# Ethernet1.net
KiCad netlist of a schematic drawn in Altium Designer
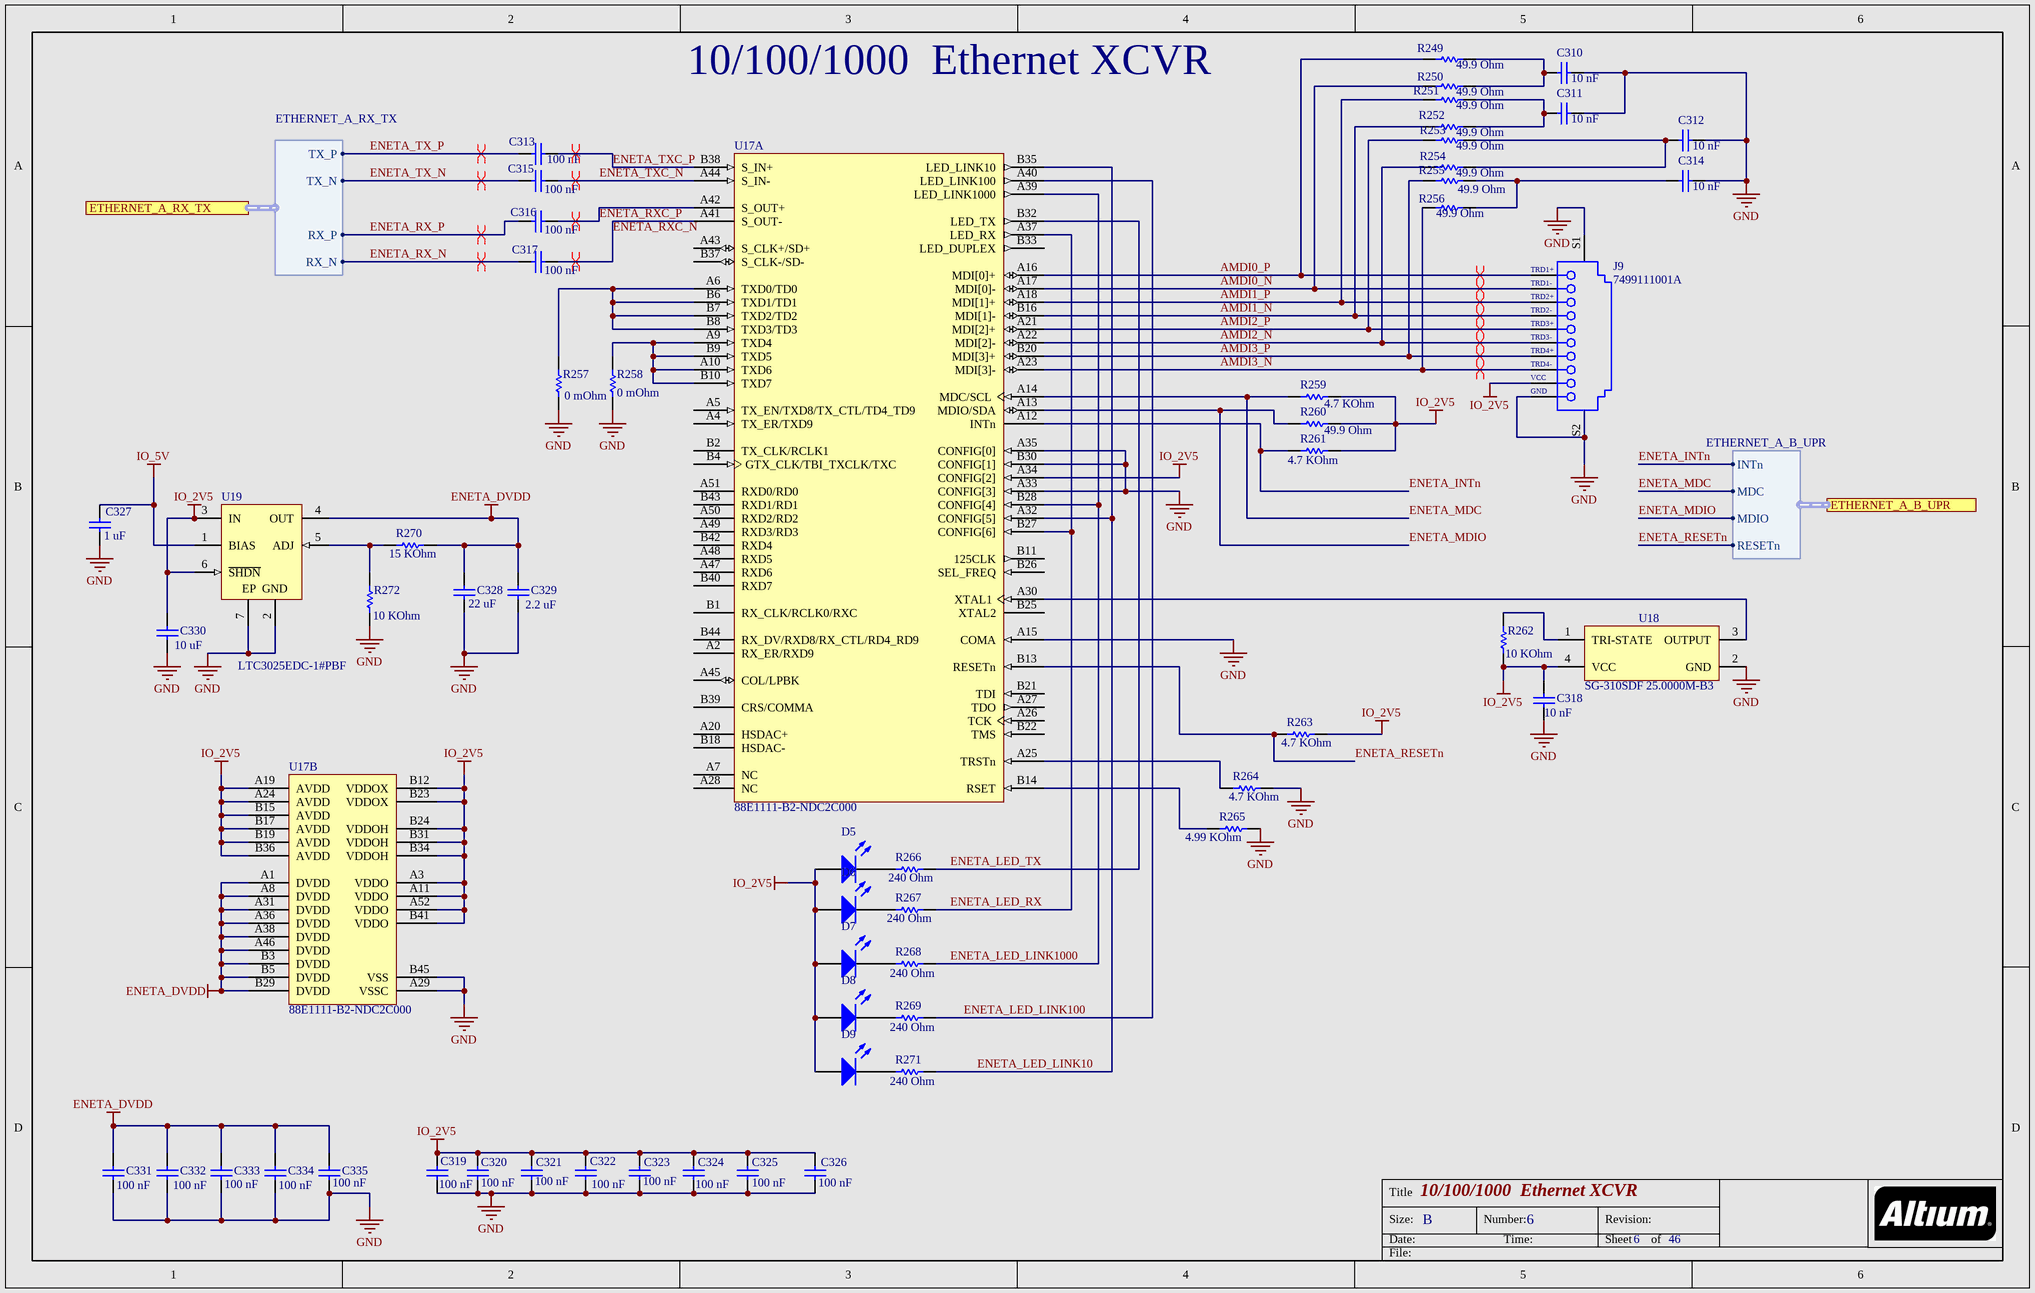
[diagram p0:  Ethernet1.SchDoc]

(export (version "E")
  (design (tool "Eeschema 10.0.6"))
  (components
    (comp (ref "C310")
      (value "GRM155R71H103KA88D")
      (footprint "CAPC1005X55X25ML05T10")
      (description "Chip Capacitor, 10 nF, +/- 10%, 50 V, -55 to 125 degC, 0402 (1005 Metric), RoHS, Tape and Reel")
      (fields
        (field (name "TOLERANCE") "10%")
        (field (name "CAPACITANCE") "10 nF")
        (field (name "MANUFACTURER") "Basic Passives")
      )
      (libsource (lib "Altium Content Vault") (part "CAP-NP-2"))
    )
    (comp (ref "C311")
      (value "GRM155R71H103KA88D")
      (footprint "CAPC1005X55X25ML05T10")
      (description "Chip Capacitor, 10 nF, +/- 10%, 50 V, -55 to 125 degC, 0402 (1005 Metric), RoHS, Tape and Reel")
      (fields
        (field (name "TOLERANCE") "10%")
        (field (name "CAPACITANCE") "10 nF")
        (field (name "MANUFACTURER") "Basic Passives")
      )
      (libsource (lib "Altium Content Vault") (part "CAP-NP-2"))
    )
    (comp (ref "C312")
      (value "GRM155R71H103KA88D")
      (footprint "CAPC1005X55X25ML05T10")
      (description "Chip Capacitor, 10 nF, +/- 10%, 50 V, -55 to 125 degC, 0402 (1005 Metric), RoHS, Tape and Reel")
      (fields
        (field (name "TOLERANCE") "10%")
        (field (name "CAPACITANCE") "10 nF")
        (field (name "MANUFACTURER") "Basic Passives")
      )
      (libsource (lib "Altium Content Vault") (part "CAP-NP-2"))
    )
    (comp (ref "C313")
      (value "C1005X7R1E104M")
      (footprint "CAPC1005X55X10LL05")
      (description "Chip Capacitor, 0.1 uF, +/- 20%, 25 V, -55 to 125 degC, 0402 (1005 Metric), RoHS, Tape and Reel")
      (fields (field (name "TOLERANCE") "20%") (field (name "CAPACITANCE") "100 nF"))
      (libsource (lib "Altium Content Vault") (part "CAP-NP-2"))
    )
    (comp (ref "C314")
      (value "GRM155R71H103KA88D")
      (footprint "CAPC1005X55X25ML05T10")
      (description "Chip Capacitor, 10 nF, +/- 10%, 50 V, -55 to 125 degC, 0402 (1005 Metric), RoHS, Tape and Reel")
      (fields
        (field (name "TOLERANCE") "10%")
        (field (name "CAPACITANCE") "10 nF")
        (field (name "MANUFACTURER") "Basic Passives")
      )
      (libsource (lib "Altium Content Vault") (part "CAP-NP-2"))
    )
    (comp (ref "C315")
      (value "C1005X7R1E104M")
      (footprint "CAPC1005X55X10LL05")
      (description "Chip Capacitor, 0.1 uF, +/- 20%, 25 V, -55 to 125 degC, 0402 (1005 Metric), RoHS, Tape and Reel")
      (fields (field (name "TOLERANCE") "20%") (field (name "CAPACITANCE") "100 nF"))
      (libsource (lib "Altium Content Vault") (part "CAP-NP-2"))
    )
    (comp (ref "C316")
      (value "C1005X7R1E104M")
      (footprint "CAPC1005X55X10LL05")
      (description "Chip Capacitor, 0.1 uF, +/- 20%, 25 V, -55 to 125 degC, 0402 (1005 Metric), RoHS, Tape and Reel")
      (fields (field (name "TOLERANCE") "20%") (field (name "CAPACITANCE") "100 nF"))
      (libsource (lib "Altium Content Vault") (part "CAP-NP-2"))
    )
    (comp (ref "C317")
      (value "C1005X7R1E104M")
      (footprint "CAPC1005X55X10LL05")
      (description "Chip Capacitor, 0.1 uF, +/- 20%, 25 V, -55 to 125 degC, 0402 (1005 Metric), RoHS, Tape and Reel")
      (fields (field (name "TOLERANCE") "20%") (field (name "CAPACITANCE") "100 nF"))
      (libsource (lib "Altium Content Vault") (part "CAP-NP-2"))
    )
    (comp (ref "C318")
      (value "GRM155R71H103KA88D")
      (footprint "CAPC1005X55X25ML05T10")
      (description "Chip Capacitor, 10 nF, +/- 10%, 50 V, -55 to 125 degC, 0402 (1005 Metric), RoHS, Tape and Reel")
      (fields
        (field (name "TOLERANCE") "10%")
        (field (name "CAPACITANCE") "10 nF")
        (field (name "MANUFACTURER") "Basic Passives")
      )
      (libsource (lib "Altium Content Vault") (part "CAP-NP-2"))
    )
    (comp (ref "C319")
      (value "C1005X7R1E104M")
      (footprint "CAPC1005X55X10LL05")
      (description "Chip Capacitor, 0.1 uF, +/- 20%, 25 V, -55 to 125 degC, 0402 (1005 Metric), RoHS, Tape and Reel")
      (fields (field (name "TOLERANCE") "20%") (field (name "CAPACITANCE") "100 nF"))
      (libsource (lib "Altium Content Vault") (part "CAP-NP-2"))
    )
    (comp (ref "C320")
      (value "C1005X7R1E104M")
      (footprint "CAPC1005X55X10LL05")
      (description "Chip Capacitor, 0.1 uF, +/- 20%, 25 V, -55 to 125 degC, 0402 (1005 Metric), RoHS, Tape and Reel")
      (fields (field (name "TOLERANCE") "20%") (field (name "CAPACITANCE") "100 nF"))
      (libsource (lib "Altium Content Vault") (part "CAP-NP-2"))
    )
    (comp (ref "C321")
      (value "C1005X7R1E104M")
      (footprint "CAPC1005X55X10LL05")
      (description "Chip Capacitor, 0.1 uF, +/- 20%, 25 V, -55 to 125 degC, 0402 (1005 Metric), RoHS, Tape and Reel")
      (fields (field (name "TOLERANCE") "20%") (field (name "CAPACITANCE") "100 nF"))
      (libsource (lib "Altium Content Vault") (part "CAP-NP-2"))
    )
    (comp (ref "C322")
      (value "C1005X7R1E104M")
      (footprint "CAPC1005X55X10LL05")
      (description "Chip Capacitor, 0.1 uF, +/- 20%, 25 V, -55 to 125 degC, 0402 (1005 Metric), RoHS, Tape and Reel")
      (fields (field (name "TOLERANCE") "20%") (field (name "CAPACITANCE") "100 nF"))
      (libsource (lib "Altium Content Vault") (part "CAP-NP-2"))
    )
    (comp (ref "C323")
      (value "C1005X7R1E104M")
      (footprint "CAPC1005X55X10LL05")
      (description "Chip Capacitor, 0.1 uF, +/- 20%, 25 V, -55 to 125 degC, 0402 (1005 Metric), RoHS, Tape and Reel")
      (fields (field (name "TOLERANCE") "20%") (field (name "CAPACITANCE") "100 nF"))
      (libsource (lib "Altium Content Vault") (part "CAP-NP-2"))
    )
    (comp (ref "C324")
      (value "C1005X7R1E104M")
      (footprint "CAPC1005X55X10LL05")
      (description "Chip Capacitor, 0.1 uF, +/- 20%, 25 V, -55 to 125 degC, 0402 (1005 Metric), RoHS, Tape and Reel")
      (fields (field (name "TOLERANCE") "20%") (field (name "CAPACITANCE") "100 nF"))
      (libsource (lib "Altium Content Vault") (part "CAP-NP-2"))
    )
    (comp (ref "C325")
      (value "C1005X7R1E104M")
      (footprint "CAPC1005X55X10LL05")
      (description "Chip Capacitor, 0.1 uF, +/- 20%, 25 V, -55 to 125 degC, 0402 (1005 Metric), RoHS, Tape and Reel")
      (fields (field (name "TOLERANCE") "20%") (field (name "CAPACITANCE") "100 nF"))
      (libsource (lib "Altium Content Vault") (part "CAP-NP-2"))
    )
    (comp (ref "C326")
      (value "C1005X7R1E104M")
      (footprint "CAPC1005X55X10LL05")
      (description "Chip Capacitor, 0.1 uF, +/- 20%, 25 V, -55 to 125 degC, 0402 (1005 Metric), RoHS, Tape and Reel")
      (fields (field (name "TOLERANCE") "20%") (field (name "CAPACITANCE") "100 nF"))
      (libsource (lib "Altium Content Vault") (part "CAP-NP-2"))
    )
    (comp (ref "C327")
      (value "CGB2A1X5R1E105K033BC")
      (footprint "CAPC1005X33X10LL5")
      (description "Chip Capacitor, 1 uF, +/- 10%, 25 V, -55 to 85 degC, 0402 (1005 Metric), RoHS, Tape and Reel")
      (fields (field (name "CAPACITANCE") "1 uF") (field (name "TOLERANCE") "10%"))
      (libsource (lib "") (part "CAP-NP-2_1"))
    )
    (comp (ref "C328")
      (value "GRM31CR61E226KE15L")
      (footprint "CAPC3216X180X55ML20T25")
      (description "Chip Capacitor, 22 uF, +/- 10%, 25 V, -55 to 85 degC, 1206 (3216 Metric), RoHS, Tape and Reel")
      (fields (field (name "TOLERANCE") "10%") (field (name "CAPACITANCE") "22 uF"))
      (libsource (lib "Altium Content Vault") (part "CAP-NP-2"))
    )
    (comp (ref "C329")
      (value "GRM188R61A225KE34x")
      (footprint "CAPC1608X90X35ML10T15")
      (description "Chip Capacitor, 2.2 uF, +/- 10%, 10 V, -55 to 85 degC, 0603 (1608 Metric), RoHS, Tape and Reel")
      (fields (field (name "TOLERANCE") "10%") (field (name "CAPACITANCE") "2.2 uF"))
      (libsource (lib "Altium Content Vault") (part "CMP-1662-00016-2"))
    )
    (comp (ref "C330")
      (value "C2012X5R1C106K085AC")
      (footprint "CAPC2013X100X20NL20")
      (description "Chip Capacitor, 10 uF, +/- 10%, 16 V, -55 to 85 degC, 0805 (2012 Metric), RoHS, Tape and Reel")
      (fields (field (name "TOLERANCE") "10%") (field (name "CAPACITANCE") "10 uF"))
      (libsource (lib "Altium Content Vault") (part "CMP-1663-00007-1"))
    )
    (comp (ref "C331")
      (value "C1005X7R1E104M")
      (footprint "CAPC1005X55X10LL05")
      (description "Chip Capacitor, 0.1 uF, +/- 20%, 25 V, -55 to 125 degC, 0402 (1005 Metric), RoHS, Tape and Reel")
      (fields (field (name "TOLERANCE") "20%") (field (name "CAPACITANCE") "100 nF"))
      (libsource (lib "Altium Content Vault") (part "CAP-NP-2"))
    )
    (comp (ref "C332")
      (value "C1005X7R1E104M")
      (footprint "CAPC1005X55X10LL05")
      (description "Chip Capacitor, 0.1 uF, +/- 20%, 25 V, -55 to 125 degC, 0402 (1005 Metric), RoHS, Tape and Reel")
      (fields (field (name "TOLERANCE") "20%") (field (name "CAPACITANCE") "100 nF"))
      (libsource (lib "Altium Content Vault") (part "CAP-NP-2"))
    )
    (comp (ref "C333")
      (value "C1005X7R1E104M")
      (footprint "CAPC1005X55X10LL05")
      (description "Chip Capacitor, 0.1 uF, +/- 20%, 25 V, -55 to 125 degC, 0402 (1005 Metric), RoHS, Tape and Reel")
      (fields (field (name "TOLERANCE") "20%") (field (name "CAPACITANCE") "100 nF"))
      (libsource (lib "Altium Content Vault") (part "CAP-NP-2"))
    )
    (comp (ref "C334")
      (value "C1005X7R1E104M")
      (footprint "CAPC1005X55X10LL05")
      (description "Chip Capacitor, 0.1 uF, +/- 20%, 25 V, -55 to 125 degC, 0402 (1005 Metric), RoHS, Tape and Reel")
      (fields (field (name "TOLERANCE") "20%") (field (name "CAPACITANCE") "100 nF"))
      (libsource (lib "Altium Content Vault") (part "CAP-NP-2"))
    )
    (comp (ref "C335")
      (value "C1005X7R1E104M")
      (footprint "CAPC1005X55X10LL05")
      (description "Chip Capacitor, 0.1 uF, +/- 20%, 25 V, -55 to 125 degC, 0402 (1005 Metric), RoHS, Tape and Reel")
      (fields (field (name "TOLERANCE") "20%") (field (name "CAPACITANCE") "100 nF"))
      (libsource (lib "Altium Content Vault") (part "CAP-NP-2"))
    )
    (comp (ref "D5")
      (value "150060VS75000")
      (footprint "0603_A")
      (description "SMD mono-color Chip LED, WL-SMCW, Bright Green")
      (fields (field (name "MANUFACTURER") "Wuerth Elektronik"))
      (libsource (lib "Altium Content Vault") (part "CMP-1426-00006-1"))
    )
    (comp (ref "D6")
      (value "150060VS75000")
      (footprint "0603_A")
      (description "SMD mono-color Chip LED, WL-SMCW, Bright Green")
      (fields (field (name "MANUFACTURER") "Wuerth Elektronik"))
      (libsource (lib "Altium Content Vault") (part "CMP-1426-00006-1"))
    )
    (comp (ref "D7")
      (value "150060VS75000")
      (footprint "0603_A")
      (description "SMD mono-color Chip LED, WL-SMCW, Bright Green")
      (fields (field (name "MANUFACTURER") "Wuerth Elektronik"))
      (libsource (lib "Altium Content Vault") (part "CMP-1426-00006-1"))
    )
    (comp (ref "D8")
      (value "150060VS75000")
      (footprint "0603_A")
      (description "SMD mono-color Chip LED, WL-SMCW, Bright Green")
      (fields (field (name "MANUFACTURER") "Wuerth Elektronik"))
      (libsource (lib "Altium Content Vault") (part "CMP-1426-00006-1"))
    )
    (comp (ref "D9")
      (value "150060VS75000")
      (footprint "0603_A")
      (description "SMD mono-color Chip LED, WL-SMCW, Bright Green")
      (fields (field (name "MANUFACTURER") "Wuerth Elektronik"))
      (libsource (lib "Altium Content Vault") (part "CMP-1426-00006-1"))
    )
    (comp (ref "J9")
      (value "7499111001A")
      (footprint "WE-7499111001A_V")
      (description "RJ45 LAN Transformer, Modular JACK, 0 to 70 degC, 10-Pin THD, RoHS, Tube")
      (libsource (lib "Altium Content Vault") (part "RJ45-10-2SHLD_A"))
    )
    (comp (ref "R249")
      (value "NRC04F49R9TRF")
      (footprint "RESC1005X35X25NL8T10")
      (description "Chip Resistor, 49.9 Ohm, +/- 1%, 0.06 W, -55 to 155 degC, 0402 (1005 Metric), RoHS, Tape and Reel")
      (fields (field (name "TOLERANCE") "1%") (field (name "RESISTANCE") "49.9 Ohm"))
      (libsource (lib "Altium Content Vault") (part "RES-2"))
    )
    (comp (ref "R250")
      (value "NRC04F49R9TRF")
      (footprint "RESC1005X35X25NL8T10")
      (description "Chip Resistor, 49.9 Ohm, +/- 1%, 0.06 W, -55 to 155 degC, 0402 (1005 Metric), RoHS, Tape and Reel")
      (fields (field (name "TOLERANCE") "1%") (field (name "RESISTANCE") "49.9 Ohm"))
      (libsource (lib "Altium Content Vault") (part "CMP-1599-00001-2"))
    )
    (comp (ref "R251")
      (value "NRC04F49R9TRF")
      (footprint "RESC1005X35X25NL8T10")
      (description "Chip Resistor, 49.9 Ohm, +/- 1%, 0.06 W, -55 to 155 degC, 0402 (1005 Metric), RoHS, Tape and Reel")
      (fields (field (name "TOLERANCE") "1%") (field (name "RESISTANCE") "49.9 Ohm"))
      (libsource (lib "Altium Content Vault") (part "CMP-1599-00001-2"))
    )
    (comp (ref "R252")
      (value "NRC04F49R9TRF")
      (footprint "RESC1005X35X25NL8T10")
      (description "Chip Resistor, 49.9 Ohm, +/- 1%, 0.06 W, -55 to 155 degC, 0402 (1005 Metric), RoHS, Tape and Reel")
      (fields (field (name "TOLERANCE") "1%") (field (name "RESISTANCE") "49.9 Ohm"))
      (libsource (lib "Altium Content Vault") (part "RES-2"))
    )
    (comp (ref "R253")
      (value "NRC04F49R9TRF")
      (footprint "RESC1005X35X25NL8T10")
      (description "Chip Resistor, 49.9 Ohm, +/- 1%, 0.06 W, -55 to 155 degC, 0402 (1005 Metric), RoHS, Tape and Reel")
      (fields (field (name "TOLERANCE") "1%") (field (name "RESISTANCE") "49.9 Ohm"))
      (libsource (lib "Altium Content Vault") (part "CMP-1599-00001-2"))
    )
    (comp (ref "R254")
      (value "NRC04F49R9TRF")
      (footprint "RESC1005X35X25NL8T10")
      (description "Chip Resistor, 49.9 Ohm, +/- 1%, 0.06 W, -55 to 155 degC, 0402 (1005 Metric), RoHS, Tape and Reel")
      (fields (field (name "TOLERANCE") "1%") (field (name "RESISTANCE") "49.9 Ohm"))
      (libsource (lib "Altium Content Vault") (part "CMP-1599-00001-2"))
    )
    (comp (ref "R255")
      (value "NRC04F49R9TRF")
      (footprint "RESC1005X35X25NL8T10")
      (description "Chip Resistor, 49.9 Ohm, +/- 1%, 0.06 W, -55 to 155 degC, 0402 (1005 Metric), RoHS, Tape and Reel")
      (fields (field (name "TOLERANCE") "1%") (field (name "RESISTANCE") "49.9 Ohm"))
      (libsource (lib "Altium Content Vault") (part "RES-2"))
    )
    (comp (ref "R256")
      (value "NRC04F49R9TRF")
      (footprint "RESC1005X35X25NL8T10")
      (description "Chip Resistor, 49.9 Ohm, +/- 1%, 0.06 W, -55 to 155 degC, 0402 (1005 Metric), RoHS, Tape and Reel")
      (fields (field (name "TOLERANCE") "1%") (field (name "RESISTANCE") "49.9 Ohm"))
      (libsource (lib "Altium Content Vault") (part "CMP-1599-00001-2"))
    )
    (comp (ref "R257")
      (value "ERJ-2GE0R00X")
      (footprint "RESC1005X40X25ML05T05")
      (description "Chip Resistor, 0 mOhm, +/- 5%, 100 mW, -55 to 155 degC, 0402 (1005 Metric), RoHS, Tape and Reel")
      (fields
        (field (name "TOLERANCE") "5%")
        (field (name "RESISTANCE") "0 mOhm")
        (field (name "MANUFACTURER") "Basic Passives")
      )
      (libsource (lib "Altium Content Vault") (part "RES-2"))
    )
    (comp (ref "R258")
      (value "ERJ-2GE0R00X")
      (footprint "RESC1005X40X25ML05T05")
      (description "Chip Resistor, 0 mOhm, +/- 5%, 100 mW, -55 to 155 degC, 0402 (1005 Metric), RoHS, Tape and Reel")
      (fields
        (field (name "TOLERANCE") "5%")
        (field (name "RESISTANCE") "0 mOhm")
        (field (name "MANUFACTURER") "Basic Passives")
      )
      (libsource (lib "Altium Content Vault") (part "RES-2"))
    )
    (comp (ref "R259")
      (value "ERJ-2RKF4701X")
      (footprint "RESC1005X40X25LL05T05")
      (description "Chip Resistor, 4.7 KOhm, +/- 1%, 0.1 W, -55 to 155 degC, 0402 (1005 Metric), RoHS, Tape and Reel")
      (fields (field (name "TOLERANCE") "1%") (field (name "RESISTANCE") "4.7 KOhm"))
      (libsource (lib "Altium Content Vault") (part "RES-2"))
    )
    (comp (ref "R260")
      (value "NRC04F49R9TRF")
      (footprint "RESC1005X35X25NL8T10")
      (description "Chip Resistor, 49.9 Ohm, +/- 1%, 0.06 W, -55 to 155 degC, 0402 (1005 Metric), RoHS, Tape and Reel")
      (fields (field (name "TOLERANCE") "1%") (field (name "RESISTANCE") "49.9 Ohm"))
      (libsource (lib "Altium Content Vault") (part "RES-2"))
    )
    (comp (ref "R261")
      (value "ERJ-2RKF4701X")
      (footprint "RESC1005X40X25LL05T05")
      (description "Chip Resistor, 4.7 KOhm, +/- 1%, 0.1 W, -55 to 155 degC, 0402 (1005 Metric), RoHS, Tape and Reel")
      (fields (field (name "TOLERANCE") "1%") (field (name "RESISTANCE") "4.7 KOhm"))
      (libsource (lib "Altium Content Vault") (part "RES-2"))
    )
    (comp (ref "R262")
      (value "ERJ-2RKF1002X")
      (footprint "RESC1005X40X25NL05T05")
      (description "Chip Resistor, 10 KOhm, +/- 1%, 100 mW, -55 to 155 degC, 0402 (1005 Metric), RoHS, Tape and Reel")
      (fields
        (field (name "TOLERANCE") "1%")
        (field (name "RESISTANCE") "10 KOhm")
        (field (name "MANUFACTURER") "Basic Passives")
      )
      (libsource (lib "Altium Content Vault") (part "RES-2"))
    )
    (comp (ref "R263")
      (value "ERJ-2RKF4701X")
      (footprint "RESC1005X40X25LL05T05")
      (description "Chip Resistor, 4.7 KOhm, +/- 1%, 0.1 W, -55 to 155 degC, 0402 (1005 Metric), RoHS, Tape and Reel")
      (fields (field (name "TOLERANCE") "1%") (field (name "RESISTANCE") "4.7 KOhm"))
      (libsource (lib "Altium Content Vault") (part "RES-2"))
    )
    (comp (ref "R264")
      (value "ERJ-2RKF4701X")
      (footprint "RESC1005X40X25LL05T05")
      (description "Chip Resistor, 4.7 KOhm, +/- 1%, 0.1 W, -55 to 155 degC, 0402 (1005 Metric), RoHS, Tape and Reel")
      (fields (field (name "TOLERANCE") "1%") (field (name "RESISTANCE") "4.7 KOhm"))
      (libsource (lib "Altium Content Vault") (part "RES-2"))
    )
    (comp (ref "R265")
      (value "ERJ-2RKF4991X")
      (footprint "RESC1005X40X25NL05T05")
      (description "Chip Resistor, 4.99 KOhm, +/- 1%, 100 mW, -55 to 155 degC, 0402 (1005 Metric), RoHS, Tape and Reel")
      (fields
        (field (name "TOLERANCE") "1%")
        (field (name "RESISTANCE") "4.99 KOhm")
        (field (name "MANUFACTURER") "Basic Passives")
      )
      (libsource (lib "Altium Content Vault") (part "RES-2"))
    )
    (comp (ref "R266")
      (value "ERJ-2RKF2400X")
      (footprint "RESC1005X40X25NL05T05")
      (description "Chip Resistor, 240 Ohm, +/- 1%, 100 mW, -55 to 155 degC, 0402 (1005 Metric), RoHS, Tape and Reel")
      (fields (field (name "TOLERANCE") "1%") (field (name "RESISTANCE") "240 Ohm"))
      (libsource (lib "Altium Content Vault") (part "RES-2"))
    )
    (comp (ref "R267")
      (value "ERJ-2RKF2400X")
      (footprint "RESC1005X40X25NL05T05")
      (description "Chip Resistor, 240 Ohm, +/- 1%, 100 mW, -55 to 155 degC, 0402 (1005 Metric), RoHS, Tape and Reel")
      (fields (field (name "TOLERANCE") "1%") (field (name "RESISTANCE") "240 Ohm"))
      (libsource (lib "Altium Content Vault") (part "RES-2"))
    )
    (comp (ref "R268")
      (value "ERJ-2RKF2400X")
      (footprint "RESC1005X40X25NL05T05")
      (description "Chip Resistor, 240 Ohm, +/- 1%, 100 mW, -55 to 155 degC, 0402 (1005 Metric), RoHS, Tape and Reel")
      (fields (field (name "TOLERANCE") "1%") (field (name "RESISTANCE") "240 Ohm"))
      (libsource (lib "Altium Content Vault") (part "RES-2"))
    )
    (comp (ref "R269")
      (value "ERJ-2RKF2400X")
      (footprint "RESC1005X40X25NL05T05")
      (description "Chip Resistor, 240 Ohm, +/- 1%, 100 mW, -55 to 155 degC, 0402 (1005 Metric), RoHS, Tape and Reel")
      (fields (field (name "TOLERANCE") "1%") (field (name "RESISTANCE") "240 Ohm"))
      (libsource (lib "Altium Content Vault") (part "RES-2"))
    )
    (comp (ref "R270")
      (value "ERJ-2RKF1502X")
      (footprint "RESC1005X40X25ML05T05")
      (description "Chip Resistor, 15 KOhm, +/- 1%, 100 mW, -55 to 155 degC, 0402 (1005 Metric), RoHS, Tape and Reel")
      (fields
        (field (name "RESISTANCE") "15 KOhm")
        (field (name "TOLERANCE") "1%")
        (field (name "MANUFACTURER") "Basic Passives")
      )
      (libsource (lib "Altium Content Vault") (part "RES-2"))
    )
    (comp (ref "R271")
      (value "ERJ-2RKF2400X")
      (footprint "RESC1005X40X25NL05T05")
      (description "Chip Resistor, 240 Ohm, +/- 1%, 100 mW, -55 to 155 degC, 0402 (1005 Metric), RoHS, Tape and Reel")
      (fields (field (name "TOLERANCE") "1%") (field (name "RESISTANCE") "240 Ohm"))
      (libsource (lib "Altium Content Vault") (part "RES-2"))
    )
    (comp (ref "R272")
      (value "ERJ-2RKF1002X")
      (footprint "RESC1005X40X25NL05T05")
      (description "Chip Resistor, 10 KOhm, +/- 1%, 100 mW, -55 to 155 degC, 0402 (1005 Metric), RoHS, Tape and Reel")
      (fields
        (field (name "TOLERANCE") "1%")
        (field (name "RESISTANCE") "10 KOhm")
        (field (name "MANUFACTURER") "Basic Passives")
      )
      (libsource (lib "Altium Content Vault") (part "RES-2"))
    )
    (comp (ref "U17")
      (value "88E1111-B2-NDC2C000")
      (footprint "MARV-NDC96")
      (description "Integrated 10/100/1000 Ultra Gigabit Ethernet Transceiver, Commercial Grade, 96-Pin QFN, RoHS")
      (libsource (lib "Altium Content Vault") (part "MARV-88E1111-NDC96"))
    )
    (comp (ref "U18")
      (value "SG-310SDF 25.0000M-B3")
      (footprint "EPSON-SG-310-4_V")
      (description "Crystal Oscillator (SPXO), 2.5 V, 25 MHz, -20 to 70 degC, 4-Pin SMD, RoHS, Tape and Reel")
      (libsource (lib "Altium Content Vault") (part "XTAL-1-3-4_B"))
    )
    (comp (ref "U19")
      (value "LTC3025EDC-1#PBF")
      (footprint "LT-DC6-6_V")
      (fields (field (name "MANUFACTURER") "Linear Technology"))
      (libsource (lib "Altium Content Vault") (part "LT-LTC302-DC6-6"))
    )
  )
  (nets
    (net (code "3") (name "/AMDI0_N") (class "Default")
      (node (ref "J9") (pin "2") (pinfunction "TRD1-_2") (pintype "passive"))
      (node (ref "R250") (pin "1") (pinfunction "1_1") (pintype "passive"))
      (node (ref "U17") (pin "A17") (pinfunction "MDI[0]-_A17") (pintype "bidirectional"))
    )
    (net (code "4") (name "/AMDI0_P") (class "Default")
      (node (ref "J9") (pin "1") (pinfunction "TRD1+_1") (pintype "passive"))
      (node (ref "R249") (pin "1") (pinfunction "1_1") (pintype "passive"))
      (node (ref "U17") (pin "A16") (pinfunction "MDI[0]+_A16") (pintype "bidirectional"))
    )
    (net (code "5") (name "/AMDI1_N") (class "Default")
      (node (ref "J9") (pin "4") (pinfunction "TRD2-_4") (pintype "passive"))
      (node (ref "R252") (pin "1") (pinfunction "1_1") (pintype "passive"))
      (node (ref "U17") (pin "B16") (pinfunction "MDI[1]-_B16") (pintype "bidirectional"))
    )
    (net (code "6") (name "/AMDI1_P") (class "Default")
      (node (ref "J9") (pin "3") (pinfunction "TRD2+_3") (pintype "passive"))
      (node (ref "R251") (pin "1") (pinfunction "1_1") (pintype "passive"))
      (node (ref "U17") (pin "A18") (pinfunction "MDI[1]+_A18") (pintype "bidirectional"))
    )
    (net (code "7") (name "/AMDI2_N") (class "Default")
      (node (ref "J9") (pin "6") (pinfunction "TRD3-_6") (pintype "passive"))
      (node (ref "R254") (pin "1") (pinfunction "1_1") (pintype "passive"))
      (node (ref "U17") (pin "A22") (pinfunction "MDI[2]-_A22") (pintype "bidirectional"))
    )
    (net (code "8") (name "/AMDI2_P") (class "Default")
      (node (ref "J9") (pin "5") (pinfunction "TRD3+_5") (pintype "passive"))
      (node (ref "R253") (pin "1") (pinfunction "1_1") (pintype "passive"))
      (node (ref "U17") (pin "A21") (pinfunction "MDI[2]+_A21") (pintype "bidirectional"))
    )
    (net (code "9") (name "/AMDI3_N") (class "Default")
      (node (ref "J9") (pin "8") (pinfunction "TRD4-_8") (pintype "passive"))
      (node (ref "R256") (pin "1") (pinfunction "1_1") (pintype "passive"))
      (node (ref "U17") (pin "A23") (pinfunction "MDI[3]-_A23") (pintype "bidirectional"))
    )
    (net (code "10") (name "/AMDI3_P") (class "Default")
      (node (ref "J9") (pin "7") (pinfunction "TRD4+_7") (pintype "passive"))
      (node (ref "R255") (pin "1") (pinfunction "1_1") (pintype "passive"))
      (node (ref "U17") (pin "B20") (pinfunction "MDI[3]+_B20") (pintype "bidirectional"))
    )
    (net (code "11") (name "/ENETA_INTn") (class "Default")
      (node (ref "R261") (pin "1") (pinfunction "1_1") (pintype "passive"))
      (node (ref "U17") (pin "A12") (pinfunction "INTn_A12") (pintype "passive"))
    )
    (net (code "12") (name "/ENETA_LED_LINK10") (class "Default")
      (node (ref "R271") (pin "2") (pinfunction "2_2") (pintype "passive"))
      (node (ref "U17") (pin "A32") (pinfunction "CONFIG[5]_A32") (pintype "input"))
      (node (ref "U17") (pin "B35") (pinfunction "LED_LINK10_B35") (pintype "output"))
    )
    (net (code "13") (name "/ENETA_LED_LINK100") (class "Default")
      (node (ref "R269") (pin "2") (pinfunction "2_2") (pintype "passive"))
      (node (ref "U17") (pin "A40") (pinfunction "LED_LINK100_A40") (pintype "output"))
    )
    (net (code "14") (name "/ENETA_LED_LINK1000") (class "Default")
      (node (ref "R268") (pin "2") (pinfunction "2_2") (pintype "passive"))
      (node (ref "U17") (pin "A39") (pinfunction "LED_LINK1000_A39") (pintype "output"))
      (node (ref "U17") (pin "B28") (pinfunction "CONFIG[4]_B28") (pintype "input"))
    )
    (net (code "15") (name "/ENETA_LED_RX") (class "Default")
      (node (ref "R267") (pin "2") (pinfunction "2_2") (pintype "passive"))
      (node (ref "U17") (pin "A37") (pinfunction "LED_RX_A37") (pintype "output"))
      (node (ref "U17") (pin "B27") (pinfunction "CONFIG[6]_B27") (pintype "input"))
    )
    (net (code "16") (name "/ENETA_LED_TX") (class "Default")
      (node (ref "R266") (pin "2") (pinfunction "2_2") (pintype "passive"))
      (node (ref "U17") (pin "B32") (pinfunction "LED_TX_B32") (pintype "output"))
    )
    (net (code "17") (name "/ENETA_MDC") (class "Default")
      (node (ref "R259") (pin "1") (pinfunction "1_1") (pintype "passive"))
      (node (ref "U17") (pin "A14") (pinfunction "MDC/SCL_A14") (pintype "input"))
    )
    (net (code "18") (name "/ENETA_MDIO") (class "Default")
      (node (ref "R260") (pin "1") (pinfunction "1_1") (pintype "passive"))
      (node (ref "U17") (pin "A13") (pinfunction "MDIO/SDA_A13") (pintype "bidirectional"))
    )
    (net (code "19") (name "/ENETA_RESETn") (class "Default")
      (node (ref "R263") (pin "1") (pinfunction "1_1") (pintype "passive"))
      (node (ref "U17") (pin "B13") (pinfunction "RESETn_B13") (pintype "input"))
    )
    (net (code "20") (name "/ENETA_RXC_N") (class "Default")
      (node (ref "C317") (pin "2") (pinfunction "2_2") (pintype "passive"))
      (node (ref "U17") (pin "A41") (pinfunction "S_OUT-_A41") (pintype "tri_state"))
    )
    (net (code "21") (name "/ENETA_RXC_P") (class "Default")
      (node (ref "C316") (pin "2") (pinfunction "2_2") (pintype "passive"))
      (node (ref "U17") (pin "A42") (pinfunction "S_OUT+_A42") (pintype "tri_state"))
    )
    (net (code "22") (name "/ENETA_RX_N") (class "Default")
      (node (ref "C317") (pin "1") (pinfunction "1_1") (pintype "passive"))
    )
    (net (code "23") (name "/ENETA_RX_P") (class "Default")
      (node (ref "C316") (pin "1") (pinfunction "1_1") (pintype "passive"))
    )
    (net (code "24") (name "/ENETA_TXC_N") (class "Default")
      (node (ref "C315") (pin "2") (pinfunction "2_2") (pintype "passive"))
      (node (ref "U17") (pin "A44") (pinfunction "S_IN-_A44") (pintype "input"))
    )
    (net (code "25") (name "/ENETA_TXC_P") (class "Default")
      (node (ref "C313") (pin "2") (pinfunction "2_2") (pintype "passive"))
      (node (ref "U17") (pin "B38") (pinfunction "S_IN+_B38") (pintype "input"))
    )
    (net (code "26") (name "/ENETA_TX_N") (class "Default")
      (node (ref "C315") (pin "1") (pinfunction "1_1") (pintype "passive"))
    )
    (net (code "27") (name "/ENETA_TX_P") (class "Default")
      (node (ref "C313") (pin "1") (pinfunction "1_1") (pintype "passive"))
    )
    (net (code "30") (name "ENETA_DVDD") (class "Default")
      (node (ref "C328") (pin "2") (pinfunction "2_2") (pintype "passive"))
      (node (ref "C329") (pin "2") (pinfunction "2_2") (pintype "passive"))
      (node (ref "C331") (pin "2") (pinfunction "2_2") (pintype "passive"))
      (node (ref "C332") (pin "2") (pinfunction "2_2") (pintype "passive"))
      (node (ref "C333") (pin "2") (pinfunction "2_2") (pintype "passive"))
      (node (ref "C334") (pin "2") (pinfunction "2_2") (pintype "passive"))
      (node (ref "C335") (pin "2") (pinfunction "2_2") (pintype "passive"))
      (node (ref "R270") (pin "2") (pinfunction "2_2") (pintype "passive"))
      (node (ref "U17") (pin "A1") (pinfunction "DVDD_A1") (pintype "power_in"))
      (node (ref "U17") (pin "A31") (pinfunction "DVDD_A31") (pintype "power_in"))
      (node (ref "U17") (pin "A36") (pinfunction "DVDD_A36") (pintype "power_in"))
      (node (ref "U17") (pin "A38") (pinfunction "DVDD_A38") (pintype "power_in"))
      (node (ref "U17") (pin "A46") (pinfunction "DVDD_A46") (pintype "power_in"))
      (node (ref "U17") (pin "A8") (pinfunction "DVDD_A8") (pintype "power_in"))
      (node (ref "U17") (pin "B29") (pinfunction "DVDD_B29") (pintype "power_in"))
      (node (ref "U17") (pin "B3") (pinfunction "DVDD_B3") (pintype "power_in"))
      (node (ref "U17") (pin "B5") (pinfunction "DVDD_B5") (pintype "power_in"))
      (node (ref "U19") (pin "4") (pinfunction "OUT_4") (pintype "power_in"))
    )
    (net (code "31") (name "GND") (class "Default")
      (node (ref "C310") (pin "2") (pinfunction "2_2") (pintype "passive"))
      (node (ref "C311") (pin "2") (pinfunction "2_2") (pintype "passive"))
      (node (ref "C312") (pin "2") (pinfunction "2_2") (pintype "passive"))
      (node (ref "C314") (pin "2") (pinfunction "2_2") (pintype "passive"))
      (node (ref "C318") (pin "1") (pinfunction "1_1") (pintype "passive"))
      (node (ref "C319") (pin "1") (pinfunction "1_1") (pintype "passive"))
      (node (ref "C320") (pin "1") (pinfunction "1_1") (pintype "passive"))
      (node (ref "C321") (pin "1") (pinfunction "1_1") (pintype "passive"))
      (node (ref "C322") (pin "1") (pinfunction "1_1") (pintype "passive"))
      (node (ref "C323") (pin "1") (pinfunction "1_1") (pintype "passive"))
      (node (ref "C324") (pin "1") (pinfunction "1_1") (pintype "passive"))
      (node (ref "C325") (pin "1") (pinfunction "1_1") (pintype "passive"))
      (node (ref "C326") (pin "1") (pinfunction "1_1") (pintype "passive"))
      (node (ref "C327") (pin "1") (pinfunction "1_1") (pintype "passive"))
      (node (ref "C328") (pin "1") (pinfunction "1_1") (pintype "passive"))
      (node (ref "C329") (pin "1") (pinfunction "1_1") (pintype "passive"))
      (node (ref "C330") (pin "1") (pinfunction "1_1") (pintype "passive"))
      (node (ref "C331") (pin "1") (pinfunction "1_1") (pintype "passive"))
      (node (ref "C332") (pin "1") (pinfunction "1_1") (pintype "passive"))
      (node (ref "C333") (pin "1") (pinfunction "1_1") (pintype "passive"))
      (node (ref "C334") (pin "1") (pinfunction "1_1") (pintype "passive"))
      (node (ref "C335") (pin "1") (pinfunction "1_1") (pintype "passive"))
      (node (ref "J9") (pin "10") (pinfunction "GND_10") (pintype "power_in"))
      (node (ref "J9") (pin "S1") (pinfunction "SHLD_S1") (pintype "passive"))
      (node (ref "J9") (pin "S2") (pinfunction "SHLD_S2") (pintype "passive"))
      (node (ref "R257") (pin "1") (pinfunction "1_1") (pintype "passive"))
      (node (ref "R258") (pin "1") (pinfunction "1_1") (pintype "passive"))
      (node (ref "R264") (pin "2") (pinfunction "2_2") (pintype "passive"))
      (node (ref "R265") (pin "2") (pinfunction "2_2") (pintype "passive"))
      (node (ref "R272") (pin "1") (pinfunction "1_1") (pintype "passive"))
      (node (ref "U17") (pin "A15") (pinfunction "COMA_A15") (pintype "input"))
      (node (ref "U17") (pin "A29") (pinfunction "VSSC_A29") (pintype "power_in"))
      (node (ref "U17") (pin "A33") (pinfunction "CONFIG[3]_A33") (pintype "input"))
      (node (ref "U17") (pin "A35") (pinfunction "CONFIG[0]_A35") (pintype "input"))
      (node (ref "U17") (pin "B30") (pinfunction "CONFIG[1]_B30") (pintype "input"))
      (node (ref "U17") (pin "B45") (pinfunction "VSS_B45") (pintype "power_in"))
      (node (ref "U18") (pin "2") (pinfunction "GND_2") (pintype "power_in"))
      (node (ref "U19") (pin "2") (pinfunction "GND_2") (pintype "power_in"))
      (node (ref "U19") (pin "7") (pinfunction "EP_7") (pintype "power_in"))
    )
    (net (code "32") (name "IO_2V5") (class "Default")
      (node (ref "C318") (pin "2") (pinfunction "2_2") (pintype "passive"))
      (node (ref "C319") (pin "2") (pinfunction "2_2") (pintype "passive"))
      (node (ref "C320") (pin "2") (pinfunction "2_2") (pintype "passive"))
      (node (ref "C321") (pin "2") (pinfunction "2_2") (pintype "passive"))
      (node (ref "C322") (pin "2") (pinfunction "2_2") (pintype "passive"))
      (node (ref "C323") (pin "2") (pinfunction "2_2") (pintype "passive"))
      (node (ref "C324") (pin "2") (pinfunction "2_2") (pintype "passive"))
      (node (ref "C325") (pin "2") (pinfunction "2_2") (pintype "passive"))
      (node (ref "C326") (pin "2") (pinfunction "2_2") (pintype "passive"))
      (node (ref "C330") (pin "2") (pinfunction "2_2") (pintype "passive"))
      (node (ref "D5") (pin "2") (pinfunction "A_2") (pintype "passive"))
      (node (ref "D6") (pin "2") (pinfunction "A_2") (pintype "passive"))
      (node (ref "D7") (pin "2") (pinfunction "A_2") (pintype "passive"))
      (node (ref "D8") (pin "2") (pinfunction "A_2") (pintype "passive"))
      (node (ref "D9") (pin "2") (pinfunction "A_2") (pintype "passive"))
      (node (ref "J9") (pin "9") (pinfunction "VCC_9") (pintype "power_in"))
      (node (ref "R259") (pin "2") (pinfunction "2_2") (pintype "passive"))
      (node (ref "R260") (pin "2") (pinfunction "2_2") (pintype "passive"))
      (node (ref "R261") (pin "2") (pinfunction "2_2") (pintype "passive"))
      (node (ref "R262") (pin "1") (pinfunction "1_1") (pintype "passive"))
      (node (ref "R263") (pin "2") (pinfunction "2_2") (pintype "passive"))
      (node (ref "U17") (pin "A11") (pinfunction "VDDO_A11") (pintype "power_in"))
      (node (ref "U17") (pin "A19") (pinfunction "AVDD_A19") (pintype "power_in"))
      (node (ref "U17") (pin "A24") (pinfunction "AVDD_A24") (pintype "power_in"))
      (node (ref "U17") (pin "A3") (pinfunction "VDDO_A3") (pintype "power_in"))
      (node (ref "U17") (pin "A34") (pinfunction "CONFIG[2]_A34") (pintype "input"))
      (node (ref "U17") (pin "A52") (pinfunction "VDDO_A52") (pintype "power_in"))
      (node (ref "U17") (pin "B12") (pinfunction "VDDOX_B12") (pintype "power_in"))
      (node (ref "U17") (pin "B15") (pinfunction "AVDD_B15") (pintype "power_in"))
      (node (ref "U17") (pin "B17") (pinfunction "AVDD_B17") (pintype "power_in"))
      (node (ref "U17") (pin "B19") (pinfunction "AVDD_B19") (pintype "power_in"))
      (node (ref "U17") (pin "B23") (pinfunction "VDDOX_B23") (pintype "power_in"))
      (node (ref "U17") (pin "B24") (pinfunction "VDDOH_B24") (pintype "power_in"))
      (node (ref "U17") (pin "B31") (pinfunction "VDDOH_B31") (pintype "power_in"))
      (node (ref "U17") (pin "B34") (pinfunction "VDDOH_B34") (pintype "power_in"))
      (node (ref "U17") (pin "B36") (pinfunction "AVDD_B36") (pintype "power_in"))
      (node (ref "U17") (pin "B41") (pinfunction "VDDO_B41") (pintype "power_in"))
      (node (ref "U18") (pin "4") (pinfunction "VCC_4") (pintype "power_in"))
      (node (ref "U19") (pin "3") (pinfunction "IN_3") (pintype "power_in"))
      (node (ref "U19") (pin "6") (pinfunction "~{SHDN}_6") (pintype "input"))
    )
    (net (code "33") (name "IO_5V") (class "Default")
      (node (ref "C327") (pin "2") (pinfunction "2_2") (pintype "passive"))
      (node (ref "U19") (pin "1") (pinfunction "BIAS_1") (pintype "power_in"))
    )
    (net (code "34") (name "Net-(C310-Pad1)") (class "Default")
      (node (ref "C310") (pin "1") (pinfunction "1_1") (pintype "passive"))
      (node (ref "R249") (pin "2") (pinfunction "2_2") (pintype "passive"))
      (node (ref "R250") (pin "2") (pinfunction "2_2") (pintype "passive"))
    )
    (net (code "35") (name "Net-(C311-Pad1)") (class "Default")
      (node (ref "C311") (pin "1") (pinfunction "1_1") (pintype "passive"))
      (node (ref "R251") (pin "2") (pinfunction "2_2") (pintype "passive"))
      (node (ref "R252") (pin "2") (pinfunction "2_2") (pintype "passive"))
    )
    (net (code "36") (name "Net-(C312-Pad1)") (class "Default")
      (node (ref "C312") (pin "1") (pinfunction "1_1") (pintype "passive"))
      (node (ref "R253") (pin "2") (pinfunction "2_2") (pintype "passive"))
      (node (ref "R254") (pin "2") (pinfunction "2_2") (pintype "passive"))
    )
    (net (code "37") (name "Net-(C314-Pad1)") (class "Default")
      (node (ref "C314") (pin "1") (pinfunction "1_1") (pintype "passive"))
      (node (ref "R255") (pin "2") (pinfunction "2_2") (pintype "passive"))
      (node (ref "R256") (pin "2") (pinfunction "2_2") (pintype "passive"))
    )
    (net (code "38") (name "Net-(D5-K)") (class "Default")
      (node (ref "D5") (pin "1") (pinfunction "K_1") (pintype "passive"))
      (node (ref "R266") (pin "1") (pinfunction "1_1") (pintype "passive"))
    )
    (net (code "39") (name "Net-(D6-K)") (class "Default")
      (node (ref "D6") (pin "1") (pinfunction "K_1") (pintype "passive"))
      (node (ref "R267") (pin "1") (pinfunction "1_1") (pintype "passive"))
    )
    (net (code "40") (name "Net-(D7-K)") (class "Default")
      (node (ref "D7") (pin "1") (pinfunction "K_1") (pintype "passive"))
      (node (ref "R268") (pin "1") (pinfunction "1_1") (pintype "passive"))
    )
    (net (code "41") (name "Net-(D8-K)") (class "Default")
      (node (ref "D8") (pin "1") (pinfunction "K_1") (pintype "passive"))
      (node (ref "R269") (pin "1") (pinfunction "1_1") (pintype "passive"))
    )
    (net (code "42") (name "Net-(D9-K)") (class "Default")
      (node (ref "D9") (pin "1") (pinfunction "K_1") (pintype "passive"))
      (node (ref "R271") (pin "1") (pinfunction "1_1") (pintype "passive"))
    )
    (net (code "43") (name "Net-(U17A-RSET)") (class "Default")
      (node (ref "R265") (pin "1") (pinfunction "1_1") (pintype "passive"))
      (node (ref "U17") (pin "B14") (pinfunction "RSET_B14") (pintype "input"))
    )
    (net (code "44") (name "Net-(U17A-TRSTn)") (class "Default")
      (node (ref "R264") (pin "1") (pinfunction "1_1") (pintype "passive"))
      (node (ref "U17") (pin "A25") (pinfunction "TRSTn_A25") (pintype "input"))
    )
    (net (code "45") (name "Net-(U17A-TXD0{slash}TD0)") (class "Default")
      (node (ref "R257") (pin "2") (pinfunction "2_2") (pintype "passive"))
      (node (ref "U17") (pin "A6") (pinfunction "TXD0/TD0_A6") (pintype "input"))
      (node (ref "U17") (pin "B6") (pinfunction "TXD1/TD1_B6") (pintype "input"))
      (node (ref "U17") (pin "B7") (pinfunction "TXD2/TD2_B7") (pintype "input"))
      (node (ref "U17") (pin "B8") (pinfunction "TXD3/TD3_B8") (pintype "input"))
    )
    (net (code "46") (name "Net-(U17A-TXD4)") (class "Default")
      (node (ref "R258") (pin "2") (pinfunction "2_2") (pintype "passive"))
      (node (ref "U17") (pin "A10") (pinfunction "TXD6_A10") (pintype "input"))
      (node (ref "U17") (pin "A9") (pinfunction "TXD4_A9") (pintype "input"))
      (node (ref "U17") (pin "B10") (pinfunction "TXD7_B10") (pintype "input"))
      (node (ref "U17") (pin "B9") (pinfunction "TXD5_B9") (pintype "input"))
    )
    (net (code "47") (name "Net-(U17A-XTAL1)") (class "Default")
      (node (ref "U17") (pin "A30") (pinfunction "XTAL1_A30") (pintype "input"))
      (node (ref "U18") (pin "3") (pinfunction "OUTPUT_3") (pintype "passive"))
    )
    (net (code "48") (name "Net-(U18-TRI-STATE)") (class "Default")
      (node (ref "R262") (pin "2") (pinfunction "2_2") (pintype "passive"))
      (node (ref "U18") (pin "1") (pinfunction "TRI-STATE_1") (pintype "passive"))
    )
    (net (code "49") (name "Net-(U19-ADJ)") (class "Default")
      (node (ref "R270") (pin "1") (pinfunction "1_1") (pintype "passive"))
      (node (ref "R272") (pin "2") (pinfunction "2_2") (pintype "passive"))
      (node (ref "U19") (pin "5") (pinfunction "ADJ_5") (pintype "input"))
    )
    (net (code "50") (name "unconnected-(U17A-125CLK-PadB11)") (class "Default")
      (node (ref "U17") (pin "B11") (pinfunction "125CLK_B11") (pintype "output"))
    )
    (net (code "51") (name "unconnected-(U17A-COL{slash}LPBK-PadA45)") (class "Default")
      (node (ref "U17") (pin "A45") (pinfunction "COL/LPBK_A45") (pintype "bidirectional"))
    )
    (net (code "52") (name "unconnected-(U17A-CRS{slash}COMMA-PadB39)") (class "Default")
      (node (ref "U17") (pin "B39") (pinfunction "CRS/COMMA_B39") (pintype "tri_state"))
    )
    (net (code "53") (name "unconnected-(U17A-GTX_CLK{slash}TBI_TXCLK{slash}TXC-PadB4)") (class "Default")
      (node (ref "U17") (pin "B4") (pinfunction "GTX_CLK/TBI_TXCLK/TXC_B4") (pintype "input"))
    )
    (net (code "54") (name "unconnected-(U17A-HSDAC+-PadA20)") (class "Default")
      (node (ref "U17") (pin "A20") (pinfunction "HSDAC+_A20") (pintype "passive"))
    )
    (net (code "55") (name "unconnected-(U17A-HSDAC--PadB18)") (class "Default")
      (node (ref "U17") (pin "B18") (pinfunction "HSDAC-_B18") (pintype "passive"))
    )
    (net (code "56") (name "unconnected-(U17A-LED_DUPLEX-PadB33)") (class "Default")
      (node (ref "U17") (pin "B33") (pinfunction "LED_DUPLEX_B33") (pintype "output"))
    )
    (net (code "57") (name "unconnected-(U17A-NC-PadA7)") (class "Default")
      (node (ref "U17") (pin "A7") (pinfunction "NC_A7") (pintype "passive"))
    )
    (net (code "58") (name "unconnected-(U17A-NC-PadA28)") (class "Default")
      (node (ref "U17") (pin "A28") (pinfunction "NC_A28") (pintype "passive"))
    )
    (net (code "59") (name "unconnected-(U17A-RXD0{slash}RD0-PadA51)") (class "Default")
      (node (ref "U17") (pin "A51") (pinfunction "RXD0/RD0_A51") (pintype "tri_state"))
    )
    (net (code "60") (name "unconnected-(U17A-RXD1{slash}RD1-PadB43)") (class "Default")
      (node (ref "U17") (pin "B43") (pinfunction "RXD1/RD1_B43") (pintype "tri_state"))
    )
    (net (code "61") (name "unconnected-(U17A-RXD2{slash}RD2-PadA50)") (class "Default")
      (node (ref "U17") (pin "A50") (pinfunction "RXD2/RD2_A50") (pintype "tri_state"))
    )
    (net (code "62") (name "unconnected-(U17A-RXD3{slash}RD3-PadA49)") (class "Default")
      (node (ref "U17") (pin "A49") (pinfunction "RXD3/RD3_A49") (pintype "tri_state"))
    )
    (net (code "63") (name "unconnected-(U17A-RXD4-PadB42)") (class "Default")
      (node (ref "U17") (pin "B42") (pinfunction "RXD4_B42") (pintype "tri_state"))
    )
    (net (code "64") (name "unconnected-(U17A-RXD5-PadA48)") (class "Default")
      (node (ref "U17") (pin "A48") (pinfunction "RXD5_A48") (pintype "tri_state"))
    )
    (net (code "65") (name "unconnected-(U17A-RXD6-PadA47)") (class "Default")
      (node (ref "U17") (pin "A47") (pinfunction "RXD6_A47") (pintype "tri_state"))
    )
    (net (code "66") (name "unconnected-(U17A-RXD7-PadB40)") (class "Default")
      (node (ref "U17") (pin "B40") (pinfunction "RXD7_B40") (pintype "tri_state"))
    )
    (net (code "67") (name "unconnected-(U17A-RX_CLK{slash}RCLK0{slash}RXC-PadB1)") (class "Default")
      (node (ref "U17") (pin "B1") (pinfunction "RX_CLK/RCLK0/RXC_B1") (pintype "tri_state"))
    )
    (net (code "68") (name "unconnected-(U17A-RX_DV{slash}RXD8{slash}RX_CTL{slash}RD4_RD9-PadB44)") (class "Default")
      (node (ref "U17") (pin "B44") (pinfunction "RX_DV/RXD8/RX_CTL/RD4_RD9_B44") (pintype "tri_state"))
    )
    (net (code "69") (name "unconnected-(U17A-RX_ER{slash}RXD9-PadA2)") (class "Default")
      (node (ref "U17") (pin "A2") (pinfunction "RX_ER/RXD9_A2") (pintype "tri_state"))
    )
    (net (code "70") (name "unconnected-(U17A-SEL_FREQ-PadB26)") (class "Default")
      (node (ref "U17") (pin "B26") (pinfunction "SEL_FREQ_B26") (pintype "input"))
    )
    (net (code "71") (name "unconnected-(U17A-S_CLK+{slash}SD+-PadA43)") (class "Default")
      (node (ref "U17") (pin "A43") (pinfunction "S_CLK+/SD+_A43") (pintype "bidirectional"))
    )
    (net (code "72") (name "unconnected-(U17A-S_CLK-{slash}SD--PadB37)") (class "Default")
      (node (ref "U17") (pin "B37") (pinfunction "S_CLK-/SD-_B37") (pintype "bidirectional"))
    )
    (net (code "73") (name "unconnected-(U17A-TCK-PadA26)") (class "Default")
      (node (ref "U17") (pin "A26") (pinfunction "TCK_A26") (pintype "input"))
    )
    (net (code "74") (name "unconnected-(U17A-TDI-PadB21)") (class "Default")
      (node (ref "U17") (pin "B21") (pinfunction "TDI_B21") (pintype "input"))
    )
    (net (code "75") (name "unconnected-(U17A-TDO-PadA27)") (class "Default")
      (node (ref "U17") (pin "A27") (pinfunction "TDO_A27") (pintype "output"))
    )
    (net (code "76") (name "unconnected-(U17A-TMS-PadB22)") (class "Default")
      (node (ref "U17") (pin "B22") (pinfunction "TMS_B22") (pintype "input"))
    )
    (net (code "77") (name "unconnected-(U17A-TX_CLK{slash}RCLK1-PadB2)") (class "Default")
      (node (ref "U17") (pin "B2") (pinfunction "TX_CLK/RCLK1_B2") (pintype "tri_state"))
    )
    (net (code "78") (name "unconnected-(U17A-TX_EN{slash}TXD8{slash}TX_CTL{slash}TD4_TD9-PadA5)") (class "Default")
      (node (ref "U17") (pin "A5") (pinfunction "TX_EN/TXD8/TX_CTL/TD4_TD9_A5") (pintype "input"))
    )
    (net (code "79") (name "unconnected-(U17A-TX_ER{slash}TXD9-PadA4)") (class "Default")
      (node (ref "U17") (pin "A4") (pinfunction "TX_ER/TXD9_A4") (pintype "input"))
    )
    (net (code "80") (name "unconnected-(U17A-XTAL2-PadB25)") (class "Default")
      (node (ref "U17") (pin "B25") (pinfunction "XTAL2_B25") (pintype "passive"))
    )
  )
)
